# 11_-_CPU_-_JTAG_CONTROL.net
KiCad netlist of a schematic drawn in Altium Designer
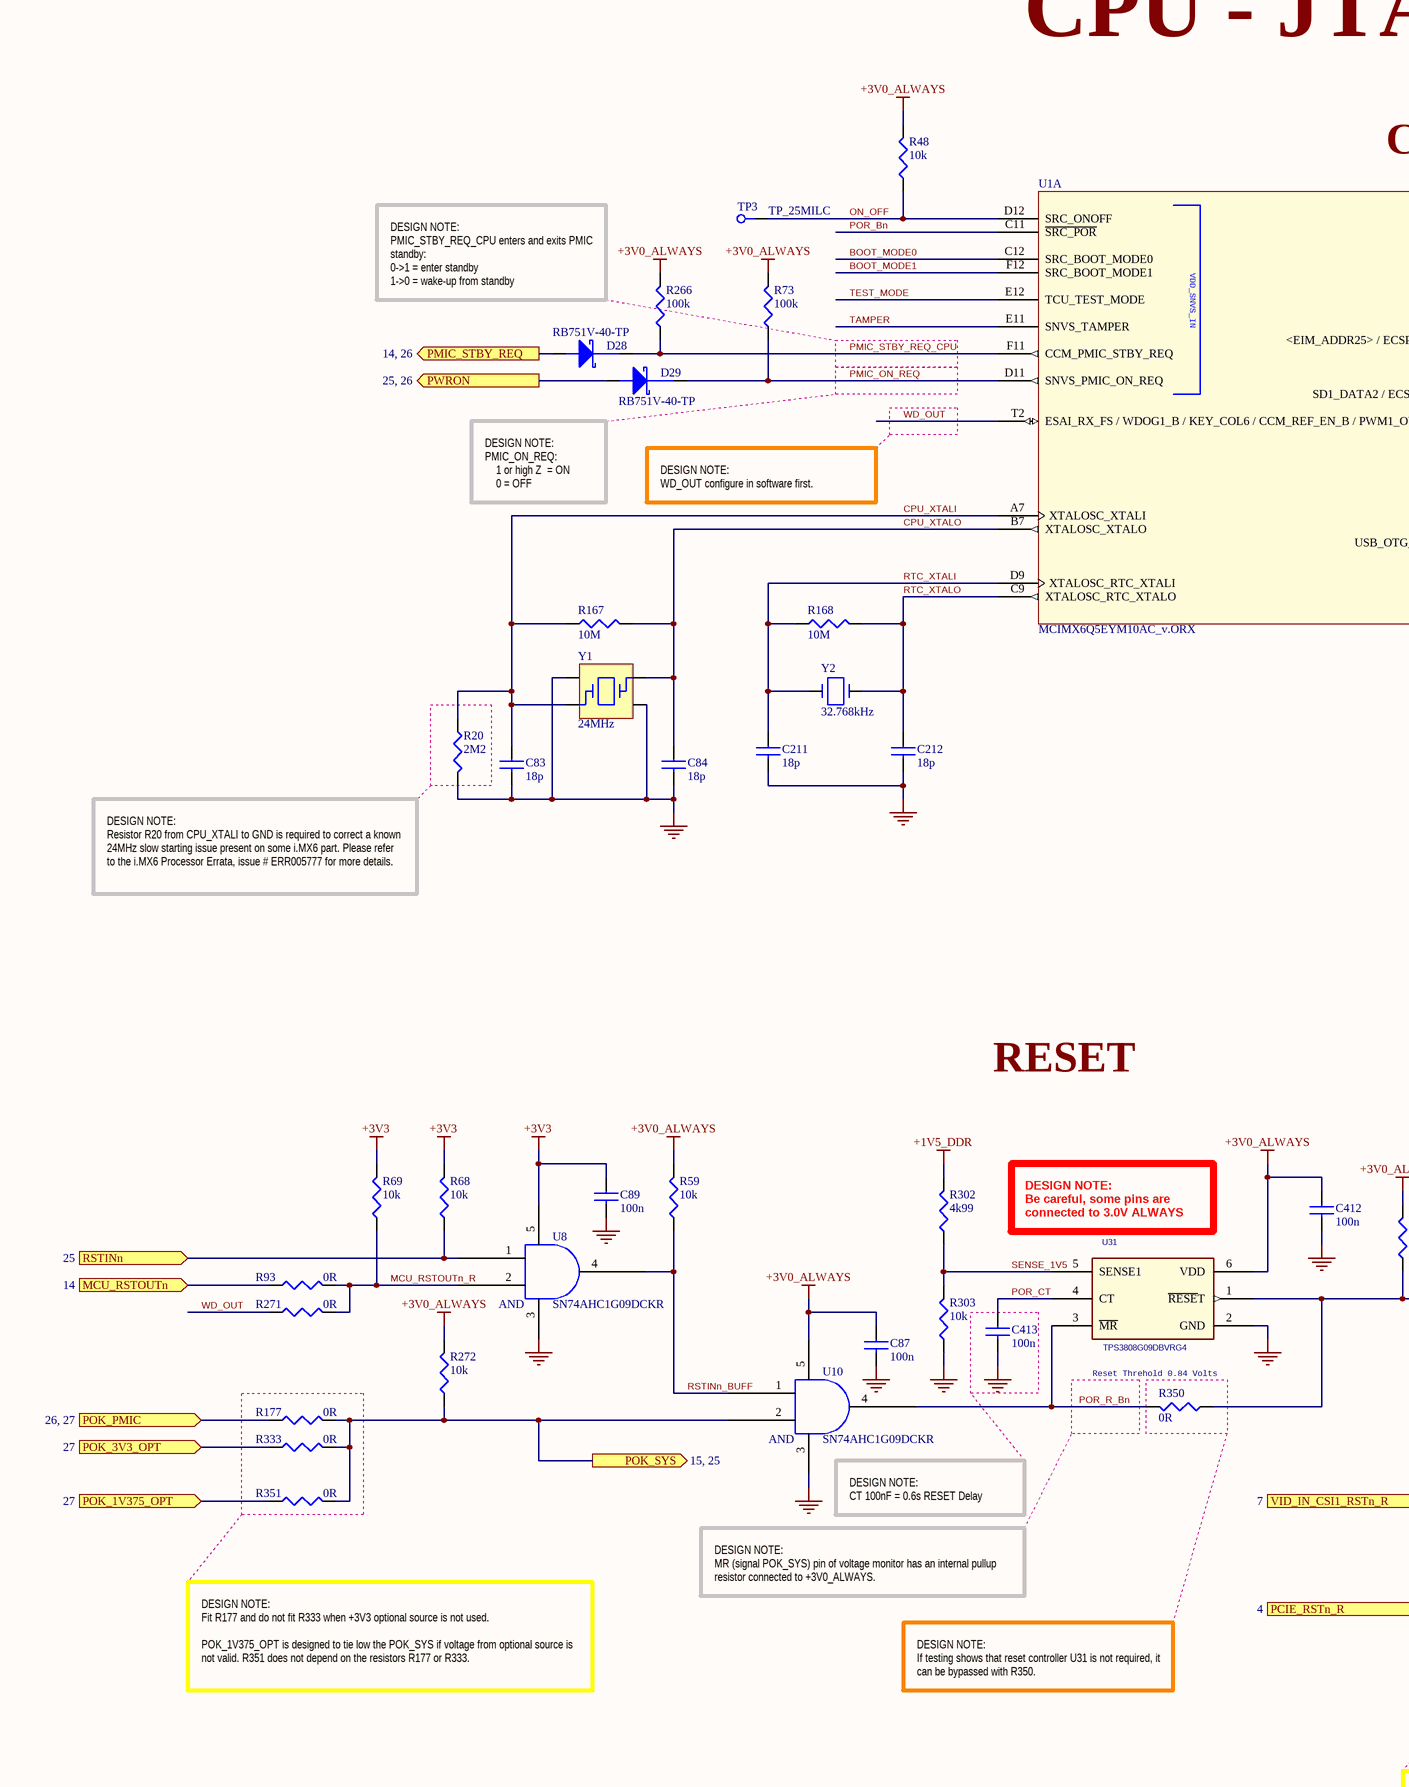
[diagram p0: [11] - CPU - JTAG, CONTROL.SchDoc, left]
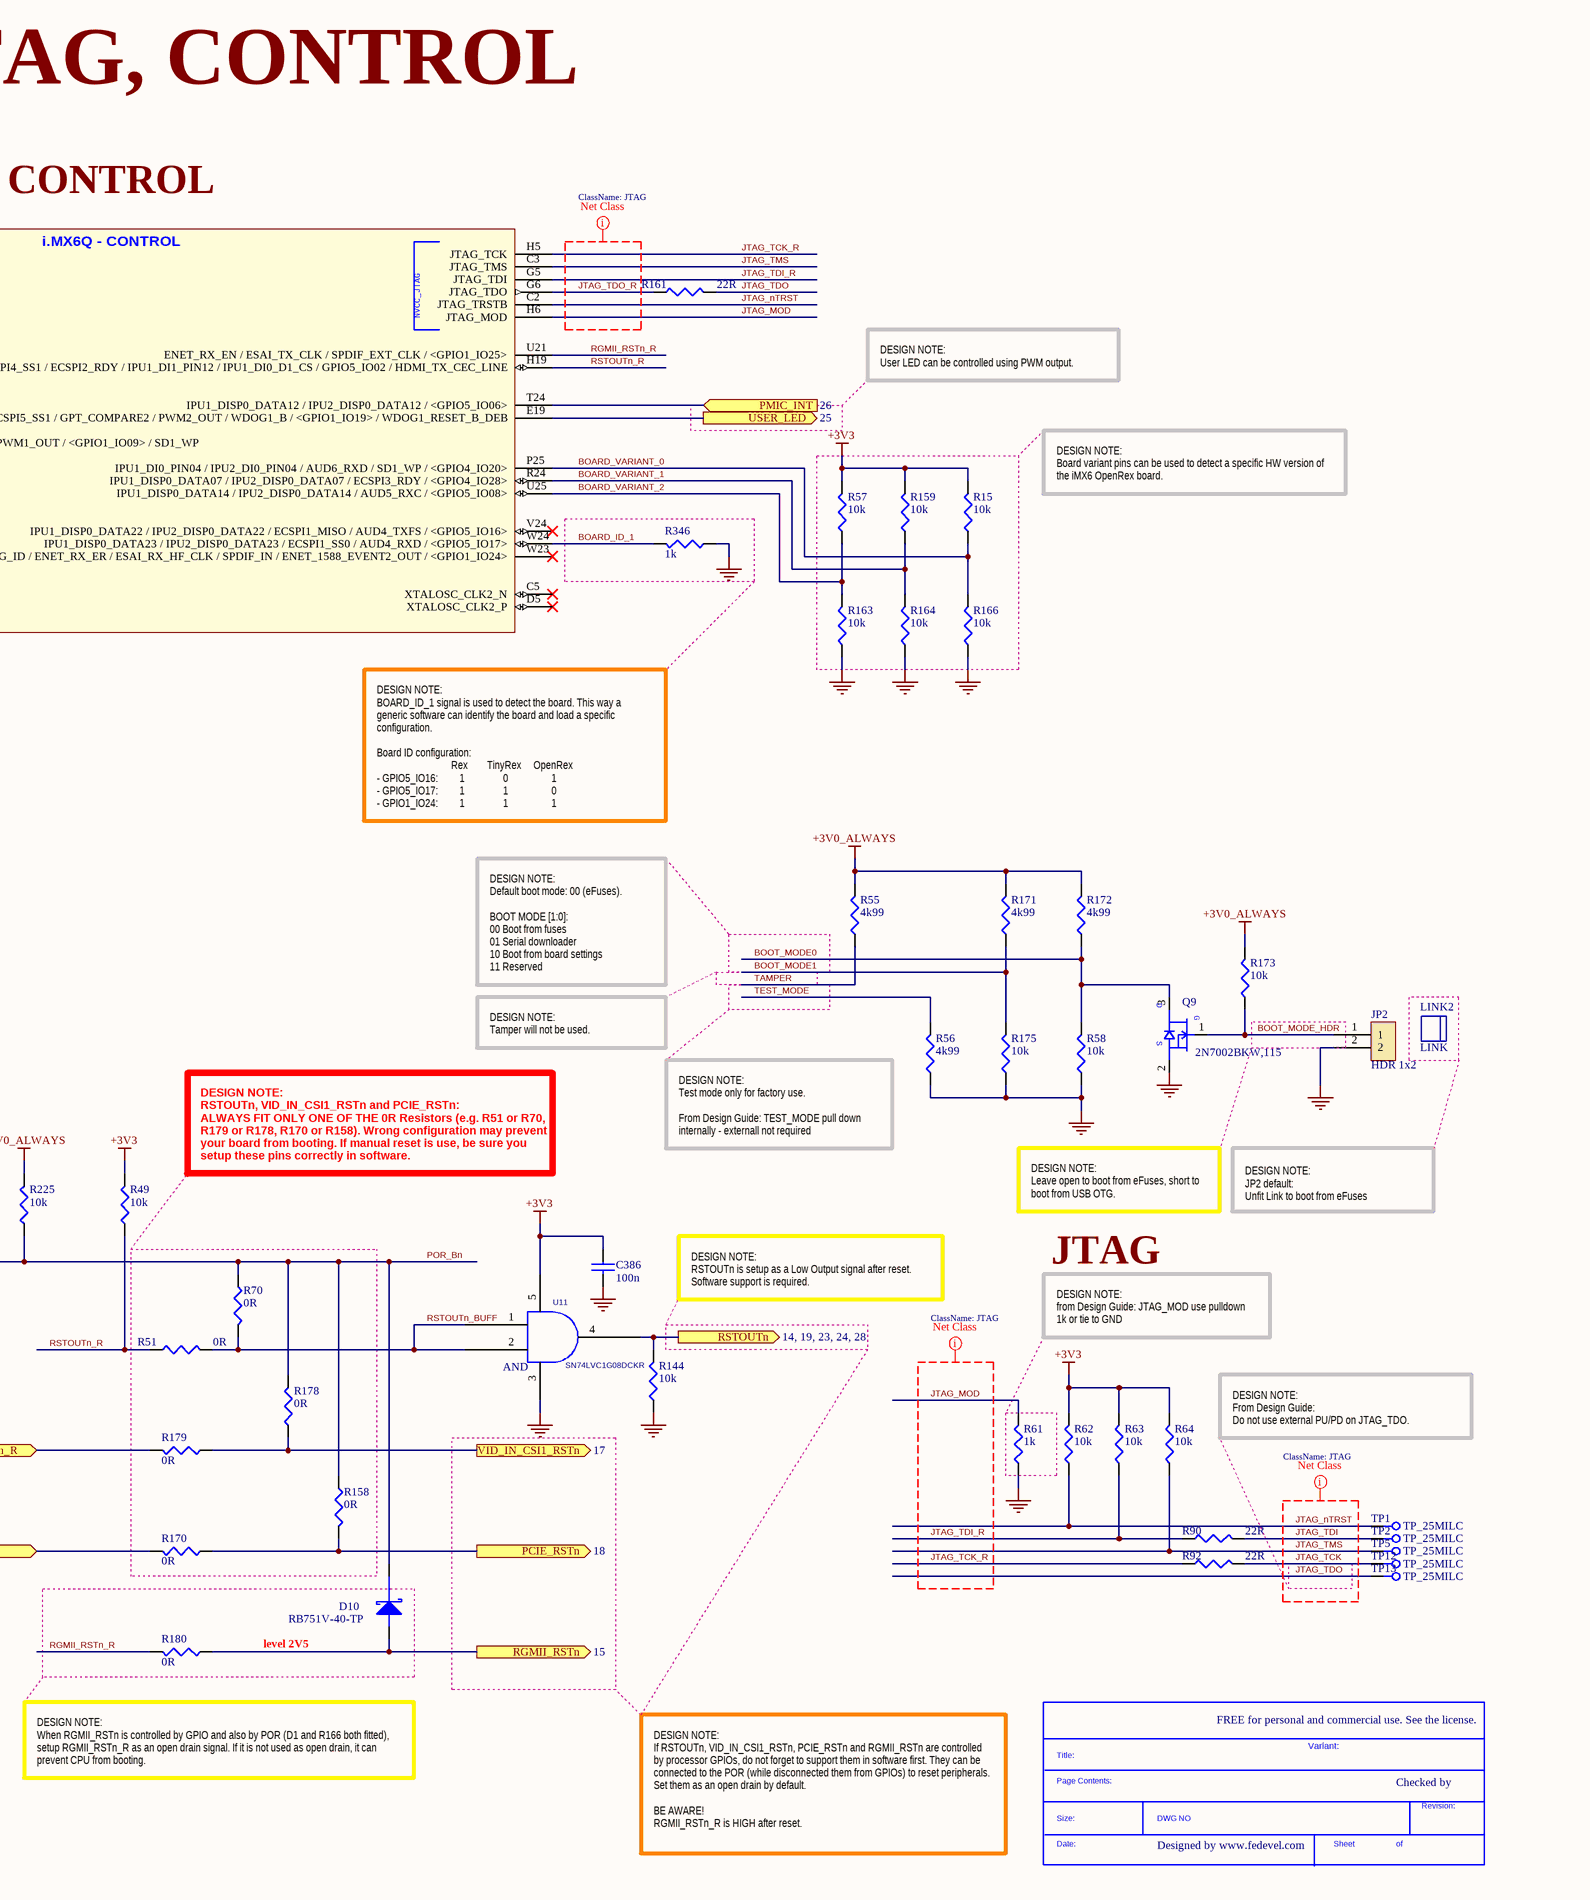
[diagram p1: [11] - CPU - JTAG, CONTROL.SchDoc, right]

(export (version "E")
  (design (tool "Eeschema 10.0.6"))
  (components
    (comp (ref "C83")
      (value "18p")
      (footprint "C0402")
      (description "CAP CER 18PF 50V C0G 5% 0402")
      (fields
        (field (name "MANUFACTURER") "TDK Corporation")
        (field (name "MANUFACTURER PART NUMBER") "C1005C0G1H180J")
      )
      (libsource (lib "Integrated_Library_FEDEVEL_APR_2015") (part "C1005C0G1H180J"))
    )
    (comp (ref "C84")
      (value "18p")
      (footprint "C0402")
      (description "CAP CER 18PF 50V C0G 5% 0402")
      (fields
        (field (name "MANUFACTURER") "TDK Corporation")
        (field (name "MANUFACTURER PART NUMBER") "C1005C0G1H180J")
      )
      (libsource (lib "Integrated_Library_FEDEVEL_APR_2015") (part "C1005C0G1H180J"))
    )
    (comp (ref "C87")
      (value "100n")
      (footprint "C0402")
      (description "CAP CER .10UF 50V X5R 10% 0402")
      (fields
        (field (name "MANUFACTURER") "TDK Corporation")
        (field (name "MANUFACTURER PART NUMBER") "C1005X5R1H104K")
      )
      (libsource (lib "Integrated_Library_FEDEVEL_APR_2015") (part "C1005X5R1H104K"))
    )
    (comp (ref "C89")
      (value "100n")
      (footprint "C0402")
      (description "CAP CER .10UF 50V X5R 10% 0402")
      (fields
        (field (name "MANUFACTURER") "TDK Corporation")
        (field (name "MANUFACTURER PART NUMBER") "C1005X5R1H104K")
      )
      (libsource (lib "Integrated_Library_FEDEVEL_APR_2015") (part "C1005X5R1H104K"))
    )
    (comp (ref "C211")
      (value "18p")
      (footprint "C0201")
      (description "CAP CER 18PF 50V 5% C0G 0201")
      (fields
        (field (name "MANUFACTURER") "TDK Corporation")
        (field (name "MANUFACTURER PART NUMBER") "C0603C0G1H180J030BA")
        (field (name ".CREATOR") "MM")
        (field (name ".CHECKED PCB") "MM")
        (field (name ".CHECKED SCH") "MM")
      )
      (libsource (lib "Integrated_Library_FEDEVEL_0201") (part "C0603C0G1H180J030BA"))
    )
    (comp (ref "C212")
      (value "18p")
      (footprint "C0201")
      (description "CAP CER 18PF 50V 5% C0G 0201")
      (fields
        (field (name "MANUFACTURER") "TDK Corporation")
        (field (name "MANUFACTURER PART NUMBER") "C0603C0G1H180J030BA")
        (field (name ".CREATOR") "MM")
        (field (name ".CHECKED PCB") "MM")
        (field (name ".CHECKED SCH") "MM")
      )
      (libsource (lib "Integrated_Library_FEDEVEL_0201") (part "C0603C0G1H180J030BA"))
    )
    (comp (ref "C386")
      (value "100n")
      (footprint "C0402")
      (description "CAP CER .10UF 50V X5R 10% 0402")
      (fields
        (field (name "MANUFACTURER") "TDK Corporation")
        (field (name "MANUFACTURER PART NUMBER") "C1005X5R1H104K")
      )
      (libsource (lib "Integrated_Library_FEDEVEL_APR_2015") (part "C1005X5R1H104K"))
    )
    (comp (ref "C412")
      (value "100n")
      (footprint "C0402")
      (description "CAP CER .10UF 50V X5R 10% 0402")
      (fields
        (field (name "MANUFACTURER") "TDK Corporation")
        (field (name "MANUFACTURER PART NUMBER") "C1005X5R1H104K")
      )
      (libsource (lib "Integrated_Library_FEDEVEL_APR_2015") (part "C1005X5R1H104K"))
    )
    (comp (ref "C413")
      (value "100n")
      (footprint "C0402")
      (description "CAP CER .10UF 50V X5R 10% 0402")
      (fields
        (field (name "MANUFACTURER") "TDK Corporation")
        (field (name "MANUFACTURER PART NUMBER") "C1005X5R1H104K")
      )
      (libsource (lib "Integrated_Library_FEDEVEL_APR_2015") (part "C1005X5R1H104K"))
    )
    (comp (ref "D10")
      (value "RB751V-40-TP")
      (footprint "SOD323")
      (description "DIODE SCHTKY 30MA 30V SOD-323")
      (fields (field (name "MANUFACTURER") "Micro Commercial Co"))
      (libsource (lib "Integrated_Library_FEDEVEL_APR_2015") (part "RB751V-40-TP"))
    )
    (comp (ref "D28")
      (value "RB751V-40-TP")
      (footprint "SOD323")
      (description "DIODE SCHTKY 30MA 30V SOD-323")
      (fields (field (name "MANUFACTURER") "Micro Commercial Co"))
      (libsource (lib "Integrated_Library_FEDEVEL_APR_2015") (part "RB751V-40-TP"))
    )
    (comp (ref "D29")
      (value "RB751V-40-TP")
      (footprint "SOD323")
      (description "DIODE SCHTKY 30MA 30V SOD-323")
      (fields (field (name "MANUFACTURER") "Micro Commercial Co"))
      (libsource (lib "Integrated_Library_FEDEVEL_APR_2015") (part "RB751V-40-TP"))
    )
    (comp (ref "JP2")
      (value "HDR 1x2")
      (footprint "HDR_1x2_2.54MM")
      (description "BERGSTIK II .100\" SR STRAIGHT")
      (fields (field (name "MANUFACTURER") "FCI") (field (name "MANUFACTURER PART NUMBER") "68001-202HLF"))
      (libsource (lib "Integrated_Library_FEDEVEL_APR_2015") (part "68001-202HLF"))
    )
    (comp (ref "LINK2")
      (value "LINK")
      (description "CONN JUMPER SHORTING .100\" GOLD")
      (fields
        (field (name "MANUFACTURER") "Sullins Connector Solutions")
        (field (name "MANUFACTURER PART NUMBER") "QPC02SXGN-RC")
      )
      (libsource (lib "Integrated_Library_FEDEVEL_APR_2015") (part "QPC02SXGN-RC"))
    )
    (comp (ref "Q9")
      (value "2N7002BKW,115")
      (footprint "SC70_SOT323")
      (description "MOSFET N-CH 60V 310MA SOT323")
      (fields (field (name "MANUFACTURER") "NXP Semiconductors"))
      (libsource (lib "Integrated_Library_FEDEVEL_APR_2015") (part "2N7002BKW,115"))
    )
    (comp (ref "R15")
      (value "10k")
      (footprint "R0402")
      (description "RES 10.0K OHM 1/16W 1% 0402 SMD")
      (fields
        (field (name "MANUFACTURER") "Yageo")
        (field (name "MANUFACTURER PART NUMBER") "RC0402FR-0710KL")
      )
      (libsource (lib "Integrated_Library_FEDEVEL_APR_2015") (part "RC0402FR-0710KL"))
    )
    (comp (ref "R20")
      (value "2M2")
      (footprint "R0402")
      (description "RES 2.20M OHM 1/16W 1% 0402 SMD")
      (fields
        (field (name "MANUFACTURER") "Vishay Dale")
        (field (name "MANUFACTURER PART NUMBER") "CRCW04022M20FKED")
        (field (name ".CREATOR") "MM")
      )
      (libsource (lib "Integrated_Library_FEDEVEL_APR_2015") (part "CRCW04022M20FKED"))
    )
    (comp (ref "R48")
      (value "10k")
      (footprint "R0402")
      (description "RES 10.0K OHM 1/16W 1% 0402 SMD")
      (fields
        (field (name "MANUFACTURER") "Yageo")
        (field (name "MANUFACTURER PART NUMBER") "RC0402FR-0710KL")
      )
      (libsource (lib "Integrated_Library_FEDEVEL_APR_2015") (part "RC0402FR-0710KL"))
    )
    (comp (ref "R49")
      (value "10k")
      (footprint "R0402")
      (description "RES 10.0K OHM 1/16W 1% 0402 SMD")
      (fields
        (field (name "MANUFACTURER") "Yageo")
        (field (name "MANUFACTURER PART NUMBER") "RC0402FR-0710KL")
      )
      (libsource (lib "Integrated_Library_FEDEVEL_APR_2015") (part "RC0402FR-0710KL"))
    )
    (comp (ref "R51")
      (value "0R")
      (footprint "R0402")
      (description "RES 0.0 OHM 1/16W 0402 SMD")
      (fields
        (field (name "MANUFACTURER") "Yageo")
        (field (name "MANUFACTURER PART NUMBER") "RC0402JR-070RL")
      )
      (libsource (lib "Integrated_Library_FEDEVEL_APR_2015") (part "RC0402JR-070RL"))
    )
    (comp (ref "R55")
      (value "4k99")
      (footprint "R0201")
      (description "RES 4.99K OHM 1/20W 1% 0201")
      (fields
        (field (name "MANUFACTURER") "Stackpole Electronics Inc")
        (field (name "MANUFACTURER PART NUMBER") "RMCF0201FT4K99")
        (field (name ".CREATOR") "MM")
        (field (name ".CHECKED PCB") "MM")
        (field (name ".CHECKED SCH") "MM")
      )
      (libsource (lib "Integrated_Library_FEDEVEL_0201") (part "RMCF0201FT4K99"))
    )
    (comp (ref "R56")
      (value "4k99")
      (footprint "R0201")
      (description "RES 4.99K OHM 1/20W 1% 0201")
      (fields
        (field (name "MANUFACTURER") "Stackpole Electronics Inc")
        (field (name "MANUFACTURER PART NUMBER") "RMCF0201FT4K99")
        (field (name ".CREATOR") "MM")
        (field (name ".CHECKED PCB") "MM")
        (field (name ".CHECKED SCH") "MM")
      )
      (libsource (lib "Integrated_Library_FEDEVEL_0201") (part "RMCF0201FT4K99"))
    )
    (comp (ref "R57")
      (value "10k")
      (footprint "R0402")
      (description "RES 10.0K OHM 1/16W 1% 0402 SMD")
      (fields
        (field (name "MANUFACTURER") "Yageo")
        (field (name "MANUFACTURER PART NUMBER") "RC0402FR-0710KL")
      )
      (libsource (lib "Integrated_Library_FEDEVEL_APR_2015") (part "RC0402FR-0710KL"))
    )
    (comp (ref "R58")
      (value "10k")
      (footprint "R0402")
      (description "RES 10.0K OHM 1/16W 1% 0402 SMD")
      (fields
        (field (name "MANUFACTURER") "Yageo")
        (field (name "MANUFACTURER PART NUMBER") "RC0402FR-0710KL")
      )
      (libsource (lib "Integrated_Library_FEDEVEL_APR_2015") (part "RC0402FR-0710KL"))
    )
    (comp (ref "R59")
      (value "10k")
      (footprint "R0402")
      (description "RES 10.0K OHM 1/16W 1% 0402 SMD")
      (fields
        (field (name "MANUFACTURER") "Yageo")
        (field (name "MANUFACTURER PART NUMBER") "RC0402FR-0710KL")
      )
      (libsource (lib "Integrated_Library_FEDEVEL_APR_2015") (part "RC0402FR-0710KL"))
    )
    (comp (ref "R61")
      (value "1k")
      (footprint "R0201")
      (description "RES 1K OHM 1/20W 1% 0201 SMD")
      (fields
        (field (name "MANUFACTURER") "Yageo")
        (field (name "MANUFACTURER PART NUMBER") "RC0201FR-071KL")
        (field (name ".CREATOR") "MM")
        (field (name ".CHECKED PCB") "MM")
        (field (name ".CHECKED SCH") "MM")
      )
      (libsource (lib "Integrated_Library_FEDEVEL_0201") (part "RC0201FR-071KL"))
    )
    (comp (ref "R62")
      (value "10k")
      (footprint "R0402")
      (description "RES 10.0K OHM 1/16W 1% 0402 SMD")
      (fields
        (field (name "MANUFACTURER") "Yageo")
        (field (name "MANUFACTURER PART NUMBER") "RC0402FR-0710KL")
      )
      (libsource (lib "Integrated_Library_FEDEVEL_APR_2015") (part "RC0402FR-0710KL"))
    )
    (comp (ref "R63")
      (value "10k")
      (footprint "R0402")
      (description "RES 10.0K OHM 1/16W 1% 0402 SMD")
      (fields
        (field (name "MANUFACTURER") "Yageo")
        (field (name "MANUFACTURER PART NUMBER") "RC0402FR-0710KL")
      )
      (libsource (lib "Integrated_Library_FEDEVEL_APR_2015") (part "RC0402FR-0710KL"))
    )
    (comp (ref "R64")
      (value "10k")
      (footprint "R0402")
      (description "RES 10.0K OHM 1/16W 1% 0402 SMD")
      (fields
        (field (name "MANUFACTURER") "Yageo")
        (field (name "MANUFACTURER PART NUMBER") "RC0402FR-0710KL")
      )
      (libsource (lib "Integrated_Library_FEDEVEL_APR_2015") (part "RC0402FR-0710KL"))
    )
    (comp (ref "R68")
      (value "10k")
      (footprint "R0402")
      (description "RES 10.0K OHM 1/16W 1% 0402 SMD")
      (fields
        (field (name "MANUFACTURER") "Yageo")
        (field (name "MANUFACTURER PART NUMBER") "RC0402FR-0710KL")
      )
      (libsource (lib "Integrated_Library_FEDEVEL_APR_2015") (part "RC0402FR-0710KL"))
    )
    (comp (ref "R69")
      (value "10k")
      (footprint "R0402")
      (description "RES 10.0K OHM 1/16W 1% 0402 SMD")
      (fields
        (field (name "MANUFACTURER") "Yageo")
        (field (name "MANUFACTURER PART NUMBER") "RC0402FR-0710KL")
      )
      (libsource (lib "Integrated_Library_FEDEVEL_APR_2015") (part "RC0402FR-0710KL"))
    )
    (comp (ref "R70")
      (value "0R")
      (footprint "R0402")
      (description "RES 0.0 OHM 1/16W 0402 SMD")
      (fields
        (field (name "MANUFACTURER") "Yageo")
        (field (name "MANUFACTURER PART NUMBER") "RC0402JR-070RL")
      )
      (libsource (lib "Integrated_Library_FEDEVEL_APR_2015") (part "RC0402JR-070RL"))
    )
    (comp (ref "R73")
      (value "100k")
      (footprint "R0402")
      (description "RES 100K OHM 1/16W 1% 0402 SMD")
      (fields
        (field (name "MANUFACTURER") "Stackpole Electronics Inc")
        (field (name "MANUFACTURER PART NUMBER") "RMCF0402FT100K")
      )
      (libsource (lib "Integrated_Library_FEDEVEL_APR_2015") (part "RMCF0402FT100K"))
    )
    (comp (ref "R90")
      (value "22R")
      (footprint "R0402")
      (description "RES 22.0 OHM 1/16W 1% 0402 SMD")
      (fields
        (field (name "MANUFACTURER") "Yageo")
        (field (name "MANUFACTURER PART NUMBER") "RC0402FR-0722RL")
      )
      (libsource (lib "Integrated_Library_FEDEVEL_APR_2015") (part "RC0402FR-0722RL"))
    )
    (comp (ref "R92")
      (value "22R")
      (footprint "R0402")
      (description "RES 22.0 OHM 1/16W 1% 0402 SMD")
      (fields
        (field (name "MANUFACTURER") "Yageo")
        (field (name "MANUFACTURER PART NUMBER") "RC0402FR-0722RL")
      )
      (libsource (lib "Integrated_Library_FEDEVEL_APR_2015") (part "RC0402FR-0722RL"))
    )
    (comp (ref "R93")
      (value "0R")
      (footprint "R0402")
      (description "RES 0.0 OHM 1/16W 0402 SMD")
      (fields
        (field (name "MANUFACTURER") "Yageo")
        (field (name "MANUFACTURER PART NUMBER") "RC0402JR-070RL")
      )
      (libsource (lib "Integrated_Library_FEDEVEL_APR_2015") (part "RC0402JR-070RL"))
    )
    (comp (ref "R144")
      (value "10k")
      (footprint "R0402")
      (description "RES 10.0K OHM 1/16W 1% 0402 SMD")
      (fields
        (field (name "MANUFACTURER") "Yageo")
        (field (name "MANUFACTURER PART NUMBER") "RC0402FR-0710KL")
      )
      (libsource (lib "Integrated_Library_FEDEVEL_APR_2015") (part "RC0402FR-0710KL"))
    )
    (comp (ref "R158")
      (value "0R")
      (footprint "R0402")
      (description "RES 0.0 OHM 1/16W 0402 SMD")
      (fields
        (field (name "MANUFACTURER") "Yageo")
        (field (name "MANUFACTURER PART NUMBER") "RC0402JR-070RL")
      )
      (libsource (lib "Integrated_Library_FEDEVEL_APR_2015") (part "RC0402JR-070RL"))
    )
    (comp (ref "R159")
      (value "10k")
      (footprint "R0402")
      (description "RES 10.0K OHM 1/16W 1% 0402 SMD")
      (fields
        (field (name "MANUFACTURER") "Yageo")
        (field (name "MANUFACTURER PART NUMBER") "RC0402FR-0710KL")
      )
      (libsource (lib "Integrated_Library_FEDEVEL_APR_2015") (part "RC0402FR-0710KL"))
    )
    (comp (ref "R161")
      (value "22R")
      (footprint "R0402")
      (description "RES 22.0 OHM 1/16W 1% 0402 SMD")
      (fields
        (field (name "MANUFACTURER") "Yageo")
        (field (name "MANUFACTURER PART NUMBER") "RC0402FR-0722RL")
      )
      (libsource (lib "Integrated_Library_FEDEVEL_APR_2015") (part "RC0402FR-0722RL"))
    )
    (comp (ref "R163")
      (value "10k")
      (footprint "R0402")
      (description "RES 10.0K OHM 1/16W 1% 0402 SMD")
      (fields
        (field (name "MANUFACTURER") "Yageo")
        (field (name "MANUFACTURER PART NUMBER") "RC0402FR-0710KL")
      )
      (libsource (lib "Integrated_Library_FEDEVEL_APR_2015") (part "RC0402FR-0710KL"))
    )
    (comp (ref "R164")
      (value "10k")
      (footprint "R0402")
      (description "RES 10.0K OHM 1/16W 1% 0402 SMD")
      (fields
        (field (name "MANUFACTURER") "Yageo")
        (field (name "MANUFACTURER PART NUMBER") "RC0402FR-0710KL")
      )
      (libsource (lib "Integrated_Library_FEDEVEL_APR_2015") (part "RC0402FR-0710KL"))
    )
    (comp (ref "R166")
      (value "10k")
      (footprint "R0402")
      (description "RES 10.0K OHM 1/16W 1% 0402 SMD")
      (fields
        (field (name "MANUFACTURER") "Yageo")
        (field (name "MANUFACTURER PART NUMBER") "RC0402FR-0710KL")
      )
      (libsource (lib "Integrated_Library_FEDEVEL_APR_2015") (part "RC0402FR-0710KL"))
    )
    (comp (ref "R167")
      (value "10M")
      (footprint "R0402")
      (description "RES 10.0M OHM 1/16W 1% 0402 SMD")
      (fields
        (field (name "MANUFACTURER") "Vishay Dale")
        (field (name "MANUFACTURER PART NUMBER") "CRCW040210M0FKED")
        (field (name ".CHECKED PCB") "RF")
        (field (name ".CHECKED SCH") "RF")
      )
      (libsource (lib "Integrated_Library_FEDEVEL_APR_2015") (part "CRCW040210M0FKED"))
    )
    (comp (ref "R168")
      (value "10M")
      (footprint "R0201")
      (description "RES 10M OHM 1/20W 1% 0201 SMD")
      (fields
        (field (name "MANUFACTURER") "Rohm Semiconductor")
        (field (name "MANUFACTURER PART NUMBER") "MCR006YZPF1005")
        (field (name ".CREATOR") "MM")
        (field (name ".CHECKED PCB") "MM")
        (field (name ".CHECKED SCH") "MM")
      )
      (libsource (lib "Integrated_Library_FEDEVEL_0201") (part "MCR006YZPF1005"))
    )
    (comp (ref "R170")
      (value "0R")
      (footprint "R0402")
      (description "RES 0.0 OHM 1/16W 0402 SMD")
      (fields
        (field (name "MANUFACTURER") "Yageo")
        (field (name "MANUFACTURER PART NUMBER") "RC0402JR-070RL")
      )
      (libsource (lib "Integrated_Library_FEDEVEL_APR_2015") (part "RC0402JR-070RL"))
    )
    (comp (ref "R171")
      (value "4k99")
      (footprint "R0402")
      (description "RES TF 4.99K OHM 1% 1/16W 0402")
      (fields
        (field (name "MANUFACTURER") "Stackpole Electronics Inc")
        (field (name "MANUFACTURER PART NUMBER") "RMCF0402FT4K99")
      )
      (libsource (lib "Integrated_Library_FEDEVEL_APR_2015") (part "RMCF0402FT4K99"))
    )
    (comp (ref "R172")
      (value "4k99")
      (footprint "R0402")
      (description "RES TF 4.99K OHM 1% 1/16W 0402")
      (fields
        (field (name "MANUFACTURER") "Stackpole Electronics Inc")
        (field (name "MANUFACTURER PART NUMBER") "RMCF0402FT4K99")
      )
      (libsource (lib "Integrated_Library_FEDEVEL_APR_2015") (part "RMCF0402FT4K99"))
    )
    (comp (ref "R173")
      (value "10k")
      (footprint "R0402")
      (description "RES 10.0K OHM 1/16W 1% 0402 SMD")
      (fields
        (field (name "MANUFACTURER") "Yageo")
        (field (name "MANUFACTURER PART NUMBER") "RC0402FR-0710KL")
      )
      (libsource (lib "Integrated_Library_FEDEVEL_APR_2015") (part "RC0402FR-0710KL"))
    )
    (comp (ref "R175")
      (value "10k")
      (footprint "R0402")
      (description "RES 10.0K OHM 1/16W 1% 0402 SMD")
      (fields
        (field (name "MANUFACTURER") "Yageo")
        (field (name "MANUFACTURER PART NUMBER") "RC0402FR-0710KL")
      )
      (libsource (lib "Integrated_Library_FEDEVEL_APR_2015") (part "RC0402FR-0710KL"))
    )
    (comp (ref "R177")
      (value "0R")
      (footprint "R0402")
      (description "RES 0.0 OHM 1/16W 0402 SMD")
      (fields
        (field (name "MANUFACTURER") "Yageo")
        (field (name "MANUFACTURER PART NUMBER") "RC0402JR-070RL")
      )
      (libsource (lib "Integrated_Library_FEDEVEL_APR_2015") (part "RC0402JR-070RL"))
    )
    (comp (ref "R178")
      (value "0R")
      (footprint "R0402")
      (description "RES 0.0 OHM 1/16W 0402 SMD")
      (fields
        (field (name "MANUFACTURER") "Yageo")
        (field (name "MANUFACTURER PART NUMBER") "RC0402JR-070RL")
      )
      (libsource (lib "Integrated_Library_FEDEVEL_APR_2015") (part "RC0402JR-070RL"))
    )
    (comp (ref "R179")
      (value "0R")
      (footprint "R0402")
      (description "RES 0.0 OHM 1/16W 0402 SMD")
      (fields
        (field (name "MANUFACTURER") "Yageo")
        (field (name "MANUFACTURER PART NUMBER") "RC0402JR-070RL")
      )
      (libsource (lib "Integrated_Library_FEDEVEL_APR_2015") (part "RC0402JR-070RL"))
    )
    (comp (ref "R180")
      (value "0R")
      (footprint "R0402")
      (description "RES 0.0 OHM 1/16W 0402 SMD")
      (fields
        (field (name "MANUFACTURER") "Yageo")
        (field (name "MANUFACTURER PART NUMBER") "RC0402JR-070RL")
      )
      (libsource (lib "Integrated_Library_FEDEVEL_APR_2015") (part "RC0402JR-070RL"))
    )
    (comp (ref "R225")
      (value "10k")
      (footprint "R0402")
      (description "RES 10.0K OHM 1/16W 1% 0402 SMD")
      (fields
        (field (name "MANUFACTURER") "Yageo")
        (field (name "MANUFACTURER PART NUMBER") "RC0402FR-0710KL")
      )
      (libsource (lib "Integrated_Library_FEDEVEL_APR_2015") (part "RC0402FR-0710KL"))
    )
    (comp (ref "R266")
      (value "100k")
      (footprint "R0402")
      (description "RES 100K OHM 1/16W 1% 0402 SMD")
      (fields
        (field (name "MANUFACTURER") "Stackpole Electronics Inc")
        (field (name "MANUFACTURER PART NUMBER") "RMCF0402FT100K")
      )
      (libsource (lib "Integrated_Library_FEDEVEL_APR_2015") (part "RMCF0402FT100K"))
    )
    (comp (ref "R271")
      (value "0R")
      (footprint "R0402")
      (description "RES 0.0 OHM 1/16W 0402 SMD")
      (fields
        (field (name "MANUFACTURER") "Yageo")
        (field (name "MANUFACTURER PART NUMBER") "RC0402JR-070RL")
      )
      (libsource (lib "Integrated_Library_FEDEVEL_APR_2015") (part "RC0402JR-070RL"))
    )
    (comp (ref "R272")
      (value "10k")
      (footprint "R0402")
      (description "RES 10.0K OHM 1/16W 1% 0402 SMD")
      (fields
        (field (name "MANUFACTURER") "Yageo")
        (field (name "MANUFACTURER PART NUMBER") "RC0402FR-0710KL")
      )
      (libsource (lib "Integrated_Library_FEDEVEL_APR_2015") (part "RC0402FR-0710KL"))
    )
    (comp (ref "R302")
      (value "4k99")
      (footprint "R0402")
      (description "RES TF 4.99K OHM 1% 1/16W 0402")
      (fields
        (field (name "MANUFACTURER") "Stackpole Electronics Inc")
        (field (name "MANUFACTURER PART NUMBER") "RMCF0402FT4K99")
      )
      (libsource (lib "Integrated_Library_FEDEVEL_APR_2015") (part "RMCF0402FT4K99"))
    )
    (comp (ref "R303")
      (value "10k")
      (footprint "R0402")
      (description "RES 10.0K OHM 1/16W 1% 0402 SMD")
      (fields
        (field (name "MANUFACTURER") "Yageo")
        (field (name "MANUFACTURER PART NUMBER") "RC0402FR-0710KL")
      )
      (libsource (lib "Integrated_Library_FEDEVEL_APR_2015") (part "RC0402FR-0710KL"))
    )
    (comp (ref "R333")
      (value "0R")
      (footprint "R0402")
      (description "RES 0.0 OHM 1/16W 0402 SMD")
      (fields
        (field (name "MANUFACTURER") "Yageo")
        (field (name "MANUFACTURER PART NUMBER") "RC0402JR-070RL")
      )
      (libsource (lib "Integrated_Library_FEDEVEL_APR_2015") (part "RC0402JR-070RL"))
    )
    (comp (ref "R346")
      (value "1k")
      (footprint "R0402")
      (description "RES 1.00K OHM 1/16W 1% 0402 SMD")
      (fields
        (field (name "MANUFACTURER") "Yageo")
        (field (name "MANUFACTURER PART NUMBER") "RC0402FR-071KL")
      )
      (libsource (lib "Integrated_Library_FEDEVEL_APR_2015") (part "RC0402FR-071KL"))
    )
    (comp (ref "R350")
      (value "0R")
      (footprint "R0402")
      (description "RES 0.0 OHM 1/16W 0402 SMD")
      (fields
        (field (name "MANUFACTURER") "Yageo")
        (field (name "MANUFACTURER PART NUMBER") "RC0402JR-070RL")
      )
      (libsource (lib "Integrated_Library_FEDEVEL_APR_2015") (part "RC0402JR-070RL"))
    )
    (comp (ref "R351")
      (value "0R")
      (footprint "R0402")
      (description "RES 0.0 OHM 1/16W 0402 SMD")
      (fields
        (field (name "MANUFACTURER") "Yageo")
        (field (name "MANUFACTURER PART NUMBER") "RC0402JR-070RL")
      )
      (libsource (lib "Integrated_Library_FEDEVEL_APR_2015") (part "RC0402JR-070RL"))
    )
    (comp (ref "TP1")
      (value "TP_25MILC")
      (footprint "TP_25C")
      (description "Test Point 25mil")
      (libsource (lib "Integrated_Library_FEDEVEL_APR_2015") (part "TP_25MILC"))
    )
    (comp (ref "TP2")
      (value "TP_25MILC")
      (footprint "TP_25C")
      (description "Test Point 25mil")
      (libsource (lib "Integrated_Library_FEDEVEL_APR_2015") (part "TP_25MILC"))
    )
    (comp (ref "TP3")
      (value "TP_25MILC")
      (footprint "TP_25C")
      (description "Test Point 25mil")
      (libsource (lib "Integrated_Library_FEDEVEL_APR_2015") (part "TP_25MILC"))
    )
    (comp (ref "TP5")
      (value "TP_25MILC")
      (footprint "TP_25C")
      (description "Test Point 25mil")
      (libsource (lib "Integrated_Library_FEDEVEL_APR_2015") (part "TP_25MILC"))
    )
    (comp (ref "TP12")
      (value "TP_25MILC")
      (footprint "TP_25C")
      (description "Test Point 25mil")
      (libsource (lib "Integrated_Library_FEDEVEL_APR_2015") (part "TP_25MILC"))
    )
    (comp (ref "TP13")
      (value "TP_25MILC")
      (footprint "TP_25C")
      (description "Test Point 25mil")
      (libsource (lib "Integrated_Library_FEDEVEL_APR_2015") (part "TP_25MILC"))
    )
    (comp (ref "U1")
      (value "MCIMX6Q5EYM10AC_v.ORX")
      (footprint "PBGA624")
      (description "IC MCU 32BIT ARM QUAD 624FCBGA")
      (fields
        (field (name "MANUFACTURER") "Freescale Semiconductor")
        (field (name "MANUFACTURER PART NUMBER") "MCIMX6Q5EYM10AC")
        (field (name ".CREATOR") "MM")
        (field (name ".CHECKED PCB") "MM, checked by RF")
      )
      (libsource (lib "Integrated_Library_FEDEVEL_APR_2015") (part "MCIMX6Q5EYM10AC_v.ORX"))
    )
    (comp (ref "U8")
      (value "SN74AHC1G09DCKR")
      (footprint "SC70_5")
      (description "IC GATE AND 1CH 2-INP SC-70-5")
      (fields
        (field (name "MANUFACTURER") "Texas Instruments")
        (field (name ".CREATOR") "MM")
        (field (name ".CHECKED SCH") "MM")
        (field (name ".CHECKED PCB") "RF, used by MM")
      )
      (libsource (lib "Integrated_Library_FEDEVEL_APR_2015") (part "SN74AHC1G09DCKR"))
    )
    (comp (ref "U10")
      (value "SN74AHC1G09DCKR")
      (footprint "SC70_5")
      (description "IC GATE AND 1CH 2-INP SC-70-5")
      (fields
        (field (name "MANUFACTURER") "Texas Instruments")
        (field (name ".CREATOR") "MM")
        (field (name ".CHECKED SCH") "MM")
        (field (name ".CHECKED PCB") "RF, used by MM")
      )
      (libsource (lib "Integrated_Library_FEDEVEL_APR_2015") (part "SN74AHC1G09DCKR"))
    )
    (comp (ref "U11")
      (value "SN74LVC1G08DCKR")
      (footprint "SC70_5")
      (description "SINGLE POSITIVE AND GATE SC-70")
      (fields (field (name "MANUFACTURER") "Texas Instruments"))
      (libsource (lib "Integrated_Library_FEDEVEL_APR_2015") (part "SN74LVC1G08DCKR"))
    )
    (comp (ref "U31")
      (value "TPS3808G09DBVRG4")
      (footprint "DBV_SOT_23_6")
      (description "IC VOLT SUPERVISOR 0.9V SOT23-6")
      (fields (field (name "PART #") "102020-0009R") (field (name "MANUFACTURER") "Texas Instruments"))
      (libsource (lib "Integrated_Library_FEDEVEL_APR_2015") (part "TPS3808G09DBVR"))
    )
    (comp (ref "Y1")
      (value "24MHz")
      (footprint "ABM8")
      (description "CRYSTAL 24MHZ 18PF SMD")
      (fields
        (field (name "MANUFACTURER") "Abracon Corporation")
        (field (name "MANUFACTURER PART NUMBER") "ABM8-24.000MHZ-R60-D-1-W-T")
        (field (name ".CREATOR") "MM")
        (field (name ".CHECKED PCB") "MM")
        (field (name ".CHECKED SCH") "MM")
      )
      (libsource (lib "Integrated_Library_FEDEVEL_APR_2015") (part "ABM8-24.000MHZ-R60-D-1-W-T"))
    )
    (comp (ref "Y2")
      (value "32.768kHz")
      (footprint "ABS06")
      (description "CRYSTAL 32.768 KHZ 9.0 PF SMD")
      (fields
        (field (name "MANUFACTURER") "Abracon Corporation")
        (field (name "MANUFACTURER PART NUMBER") "ABS06-32.768KHZ-9-1-T")
      )
      (libsource (lib "Integrated_Library_FEDEVEL_APR_2015") (part "ABS06-32.768KHZ-9-1-T"))
    )
  )
  (nets
    (net (code "1") (name "+1V5_DDR") (class "Default")
      (node (ref "R302") (pin "2") (pinfunction "2_2") (pintype "passive"))
    )
    (net (code "2") (name "+3V0_ALWAYS") (class "Default")
      (node (ref "C412") (pin "1") (pinfunction "1_1") (pintype "passive"))
      (node (ref "C87") (pin "1") (pinfunction "1_1") (pintype "passive"))
      (node (ref "R171") (pin "2") (pinfunction "2_2") (pintype "passive"))
      (node (ref "R172") (pin "2") (pinfunction "2_2") (pintype "passive"))
      (node (ref "R173") (pin "2") (pinfunction "2_2") (pintype "passive"))
      (node (ref "R225") (pin "2") (pinfunction "2_2") (pintype "passive"))
      (node (ref "R266") (pin "2") (pinfunction "2_2") (pintype "passive"))
      (node (ref "R272") (pin "2") (pinfunction "2_2") (pintype "passive"))
      (node (ref "R48") (pin "2") (pinfunction "2_2") (pintype "passive"))
      (node (ref "R55") (pin "2") (pinfunction "2_2") (pintype "passive"))
      (node (ref "R59") (pin "2") (pinfunction "2_2") (pintype "passive"))
      (node (ref "R73") (pin "2") (pinfunction "2_2") (pintype "passive"))
      (node (ref "U10") (pin "5") (pinfunction "VCC_5") (pintype "power_in"))
      (node (ref "U31") (pin "6") (pinfunction "VDD_6") (pintype "passive"))
    )
    (net (code "3") (name "+3V3") (class "Default")
      (node (ref "C386") (pin "1") (pinfunction "1_1") (pintype "passive"))
      (node (ref "C89") (pin "1") (pinfunction "1_1") (pintype "passive"))
      (node (ref "R15") (pin "2") (pinfunction "2_2") (pintype "passive"))
      (node (ref "R159") (pin "2") (pinfunction "2_2") (pintype "passive"))
      (node (ref "R49") (pin "2") (pinfunction "2_2") (pintype "passive"))
      (node (ref "R57") (pin "2") (pinfunction "2_2") (pintype "passive"))
      (node (ref "R62") (pin "2") (pinfunction "2_2") (pintype "passive"))
      (node (ref "R63") (pin "2") (pinfunction "2_2") (pintype "passive"))
      (node (ref "R64") (pin "2") (pinfunction "2_2") (pintype "passive"))
      (node (ref "R68") (pin "2") (pinfunction "2_2") (pintype "passive"))
      (node (ref "R69") (pin "2") (pinfunction "2_2") (pintype "passive"))
      (node (ref "U11") (pin "5") (pinfunction "VCC_5") (pintype "power_in"))
      (node (ref "U8") (pin "5") (pinfunction "VCC_5") (pintype "power_in"))
    )
    (net (code "4") (name "/BOARD_ID_1") (class "Default")
      (node (ref "R346") (pin "2") (pinfunction "2_2") (pintype "passive"))
      (node (ref "U1") (pin "W24") (pinfunction "IPU1_DISP0_DATA23_/_IPU2_DISP0_DATA23_/_ECSPI1_SS0_/_AUD4_RXD_/_<GPIO5_IO17>_W24") (pintype "bidirectional"))
    )
    (net (code "5") (name "/BOARD_VARIANT_0") (class "Default")
      (node (ref "R15") (pin "1") (pinfunction "1_1") (pintype "passive"))
      (node (ref "R166") (pin "2") (pinfunction "2_2") (pintype "passive"))
      (node (ref "U1") (pin "P25") (pinfunction "IPU1_DI0_PIN04_/_IPU2_DI0_PIN04_/_AUD6_RXD_/_SD1_WP_/_<GPIO4_IO20>_P25") (pintype "passive"))
    )
    (net (code "6") (name "/BOARD_VARIANT_1") (class "Default")
      (node (ref "R159") (pin "1") (pinfunction "1_1") (pintype "passive"))
      (node (ref "R164") (pin "2") (pinfunction "2_2") (pintype "passive"))
      (node (ref "U1") (pin "R24") (pinfunction "IPU1_DISP0_DATA07_/_IPU2_DISP0_DATA07_/_ECSPI3_RDY_/_<GPIO4_IO28>_R24") (pintype "bidirectional"))
    )
    (net (code "7") (name "/BOARD_VARIANT_2") (class "Default")
      (node (ref "R163") (pin "2") (pinfunction "2_2") (pintype "passive"))
      (node (ref "R57") (pin "1") (pinfunction "1_1") (pintype "passive"))
      (node (ref "U1") (pin "U25") (pinfunction "IPU1_DISP0_DATA14_/_IPU2_DISP0_DATA14_/_AUD5_RXC_/_<GPIO5_IO08>_U25") (pintype "bidirectional"))
    )
    (net (code "8") (name "/BOOT_MODE0") (class "Default")
      (node (ref "Q9") (pin "3") (pinfunction "DRAIN_3") (pintype "passive"))
      (node (ref "R172") (pin "1") (pinfunction "1_1") (pintype "passive"))
      (node (ref "R58") (pin "2") (pinfunction "2_2") (pintype "passive"))
      (node (ref "U1") (pin "C12") (pinfunction "SRC_BOOT_MODE0_C12") (pintype "passive"))
    )
    (net (code "9") (name "/BOOT_MODE1") (class "Default")
      (node (ref "R171") (pin "1") (pinfunction "1_1") (pintype "passive"))
      (node (ref "R175") (pin "2") (pinfunction "2_2") (pintype "passive"))
      (node (ref "U1") (pin "F12") (pinfunction "SRC_BOOT_MODE1_F12") (pintype "passive"))
    )
    (net (code "10") (name "/BOOT_MODE_HDR") (class "Default")
      (node (ref "JP2") (pin "1") (pinfunction "1_1") (pintype "passive"))
      (node (ref "Q9") (pin "1") (pinfunction "GATE_1") (pintype "passive"))
      (node (ref "R173") (pin "1") (pinfunction "1_1") (pintype "passive"))
    )
    (net (code "11") (name "/CPU_XTALI") (class "Default")
      (node (ref "C83") (pin "1") (pinfunction "1_1") (pintype "passive"))
      (node (ref "R167") (pin "1") (pinfunction "1_1") (pintype "passive"))
      (node (ref "R20") (pin "1") (pinfunction "1_1") (pintype "passive"))
      (node (ref "U1") (pin "A7") (pinfunction "XTALOSC_XTALI_A7") (pintype "passive"))
      (node (ref "Y1") (pin "3") (pinfunction "3_3") (pintype "passive"))
    )
    (net (code "12") (name "/CPU_XTALO") (class "Default")
      (node (ref "C84") (pin "1") (pinfunction "1_1") (pintype "passive"))
      (node (ref "R167") (pin "2") (pinfunction "2_2") (pintype "passive"))
      (node (ref "U1") (pin "B7") (pinfunction "XTALOSC_XTALO_B7") (pintype "output"))
      (node (ref "Y1") (pin "1") (pinfunction "1_1") (pintype "passive"))
    )
    (net (code "13") (name "/JTAG_MOD") (class "Default")
      (node (ref "R61") (pin "2") (pinfunction "2_2") (pintype "passive"))
      (node (ref "U1") (pin "H6") (pinfunction "JTAG_MOD_H6") (pintype "passive"))
    )
    (net (code "14") (name "/JTAG_TCK") (class "Default")
      (node (ref "R92") (pin "2") (pinfunction "2_2") (pintype "passive"))
      (node (ref "TP12") (pin "1") (pinfunction "1_1") (pintype "passive"))
    )
    (net (code "15") (name "/JTAG_TCK_R") (class "Default")
      (node (ref "R92") (pin "1") (pinfunction "1_1") (pintype "passive"))
      (node (ref "U1") (pin "H5") (pinfunction "JTAG_TCK_H5") (pintype "passive"))
    )
    (net (code "16") (name "/JTAG_TDI") (class "Default")
      (node (ref "R90") (pin "2") (pinfunction "2_2") (pintype "passive"))
      (node (ref "TP2") (pin "1") (pinfunction "1_1") (pintype "passive"))
    )
    (net (code "17") (name "/JTAG_TDI_R") (class "Default")
      (node (ref "R63") (pin "1") (pinfunction "1_1") (pintype "passive"))
      (node (ref "R90") (pin "1") (pinfunction "1_1") (pintype "passive"))
      (node (ref "U1") (pin "G5") (pinfunction "JTAG_TDI_G5") (pintype "passive"))
    )
    (net (code "18") (name "/JTAG_TDO") (class "Default")
      (node (ref "R161") (pin "2") (pinfunction "2_2") (pintype "passive"))
      (node (ref "TP13") (pin "1") (pinfunction "1_1") (pintype "passive"))
    )
    (net (code "19") (name "/JTAG_TDO_R") (class "Default")
      (node (ref "R161") (pin "1") (pinfunction "1_1") (pintype "passive"))
      (node (ref "U1") (pin "G6") (pinfunction "JTAG_TDO_G6") (pintype "output"))
    )
    (net (code "20") (name "/JTAG_TMS") (class "Default")
      (node (ref "R64") (pin "1") (pinfunction "1_1") (pintype "passive"))
      (node (ref "TP5") (pin "1") (pinfunction "1_1") (pintype "passive"))
      (node (ref "U1") (pin "C3") (pinfunction "JTAG_TMS_C3") (pintype "passive"))
    )
    (net (code "21") (name "/JTAG_nTRST") (class "Default")
      (node (ref "R62") (pin "1") (pinfunction "1_1") (pintype "passive"))
      (node (ref "TP1") (pin "1") (pinfunction "1_1") (pintype "passive"))
      (node (ref "U1") (pin "C2") (pinfunction "JTAG_TRSTB_C2") (pintype "passive"))
    )
    (net (code "22") (name "/MCU_RSTOUTn") (class "Default")
      (node (ref "R93") (pin "1") (pinfunction "1_1") (pintype "passive"))
    )
    (net (code "23") (name "/MCU_RSTOUTn_R") (class "Default")
      (node (ref "R271") (pin "2") (pinfunction "2_2") (pintype "passive"))
      (node (ref "R69") (pin "1") (pinfunction "1_1") (pintype "passive"))
      (node (ref "R93") (pin "2") (pinfunction "2_2") (pintype "passive"))
      (node (ref "U8") (pin "2") (pinfunction "B_2") (pintype "passive"))
    )
    (net (code "24") (name "/ON_OFF") (class "Default")
      (node (ref "R48") (pin "1") (pinfunction "1_1") (pintype "passive"))
      (node (ref "TP3") (pin "1") (pinfunction "1_1") (pintype "passive"))
      (node (ref "U1") (pin "D12") (pinfunction "SRC_ONOFF_D12") (pintype "passive"))
    )
    (net (code "25") (name "/PCIE_RSTn") (class "Default")
      (node (ref "R158") (pin "2") (pinfunction "2_2") (pintype "passive"))
      (node (ref "R170") (pin "1") (pinfunction "1_1") (pintype "passive"))
    )
    (net (code "26") (name "/PCIE_RSTn_R") (class "Default")
      (node (ref "R170") (pin "2") (pinfunction "2_2") (pintype "passive"))
    )
    (net (code "27") (name "/PMIC_INT") (class "Default")
      (node (ref "U1") (pin "T24") (pinfunction "IPU1_DISP0_DATA12_/_IPU2_DISP0_DATA12_/_<GPIO5_IO06>_T24") (pintype "passive"))
    )
    (net (code "28") (name "/PMIC_ON_REQ") (class "Default")
      (node (ref "D29") (pin "1") (pinfunction "cathode_1") (pintype "passive"))
      (node (ref "R73") (pin "1") (pinfunction "1_1") (pintype "passive"))
      (node (ref "U1") (pin "D11") (pinfunction "SNVS_PMIC_ON_REQ_D11") (pintype "output"))
    )
    (net (code "29") (name "/PMIC_STBY_REQ") (class "Default")
      (node (ref "D28") (pin "2") (pinfunction "ANODE_2") (pintype "passive"))
    )
    (net (code "30") (name "/PMIC_STBY_REQ_CPU") (class "Default")
      (node (ref "D28") (pin "1") (pinfunction "cathode_1") (pintype "passive"))
      (node (ref "R266") (pin "1") (pinfunction "1_1") (pintype "passive"))
      (node (ref "U1") (pin "F11") (pinfunction "CCM_PMIC_STBY_REQ_F11") (pintype "output"))
    )
    (net (code "31") (name "/POK_1V375_OPT") (class "Default")
      (node (ref "R351") (pin "1") (pinfunction "1_1") (pintype "passive"))
    )
    (net (code "32") (name "/POK_3V3_OPT") (class "Default")
      (node (ref "R333") (pin "1") (pinfunction "1_1") (pintype "passive"))
    )
    (net (code "33") (name "/POK_PMIC") (class "Default")
      (node (ref "R177") (pin "1") (pinfunction "1_1") (pintype "passive"))
    )
    (net (code "34") (name "/POK_SYS") (class "Default")
      (node (ref "R177") (pin "2") (pinfunction "2_2") (pintype "passive"))
      (node (ref "R272") (pin "1") (pinfunction "1_1") (pintype "passive"))
      (node (ref "R333") (pin "2") (pinfunction "2_2") (pintype "passive"))
      (node (ref "R351") (pin "2") (pinfunction "2_2") (pintype "passive"))
      (node (ref "U10") (pin "2") (pinfunction "B_2") (pintype "passive"))
    )
    (net (code "35") (name "/POR_Bn") (class "Default")
      (node (ref "D10") (pin "1") (pinfunction "cathode_1") (pintype "passive"))
      (node (ref "R158") (pin "1") (pinfunction "1_1") (pintype "passive"))
      (node (ref "R178") (pin "2") (pinfunction "2_2") (pintype "passive"))
      (node (ref "R225") (pin "1") (pinfunction "1_1") (pintype "passive"))
      (node (ref "R350") (pin "1") (pinfunction "1_1") (pintype "passive"))
      (node (ref "R70") (pin "1") (pinfunction "1_1") (pintype "passive"))
      (node (ref "U1") (pin "C11") (pinfunction "~{SRC_POR}_C11") (pintype "passive"))
      (node (ref "U31") (pin "1") (pinfunction "~{RESE}T_1") (pintype "output"))
    )
    (net (code "36") (name "/POR_CT") (class "Default")
      (node (ref "C413") (pin "1") (pinfunction "1_1") (pintype "passive"))
      (node (ref "U31") (pin "4") (pinfunction "CT_4") (pintype "passive"))
    )
    (net (code "37") (name "/POR_R_Bn") (class "Default")
      (node (ref "R350") (pin "2") (pinfunction "2_2") (pintype "passive"))
      (node (ref "U10") (pin "4") (pinfunction "Y_4") (pintype "passive"))
      (node (ref "U31") (pin "3") (pinfunction "~{MR}_3") (pintype "passive"))
    )
    (net (code "38") (name "/PWRON") (class "Default")
      (node (ref "D29") (pin "2") (pinfunction "ANODE_2") (pintype "passive"))
    )
    (net (code "39") (name "/RGMII_RSTn") (class "Default")
      (node (ref "D10") (pin "2") (pinfunction "ANODE_2") (pintype "passive"))
      (node (ref "R180") (pin "1") (pinfunction "1_1") (pintype "passive"))
    )
    (net (code "40") (name "/RGMII_RSTn_R") (class "Default")
      (node (ref "R180") (pin "2") (pinfunction "2_2") (pintype "passive"))
      (node (ref "U1") (pin "U21") (pinfunction "ENET_RX_EN_/_ESAI_TX_CLK_/_SPDIF_EXT_CLK_/_<GPIO1_IO25>_U21") (pintype "passive"))
    )
    (net (code "41") (name "/RSTINn") (class "Default")
      (node (ref "R68") (pin "1") (pinfunction "1_1") (pintype "passive"))
      (node (ref "U8") (pin "1") (pinfunction "A_1") (pintype "passive"))
    )
    (net (code "42") (name "/RSTINn_BUFF") (class "Default")
      (node (ref "R59") (pin "1") (pinfunction "1_1") (pintype "passive"))
      (node (ref "U10") (pin "1") (pinfunction "A_1") (pintype "passive"))
      (node (ref "U8") (pin "4") (pinfunction "Y_4") (pintype "passive"))
    )
    (net (code "43") (name "/RSTOUTn") (class "Default")
      (node (ref "R144") (pin "2") (pinfunction "2_2") (pintype "passive"))
      (node (ref "U11") (pin "4") (pinfunction "Y_4") (pintype "passive"))
    )
    (net (code "44") (name "/RSTOUTn_BUFF") (class "Default")
      (node (ref "R51") (pin "2") (pinfunction "2_2") (pintype "passive"))
      (node (ref "R70") (pin "2") (pinfunction "2_2") (pintype "passive"))
      (node (ref "U11") (pin "1") (pinfunction "A_1") (pintype "passive"))
      (node (ref "U11") (pin "2") (pinfunction "B_2") (pintype "passive"))
    )
    (net (code "45") (name "/RSTOUTn_R") (class "Default")
      (node (ref "R49") (pin "1") (pinfunction "1_1") (pintype "passive"))
      (node (ref "R51") (pin "1") (pinfunction "1_1") (pintype "passive"))
      (node (ref "U1") (pin "H19") (pinfunction "<EIM_ADDR25>_/_ECSPI4_SS1_/_ECSPI2_RDY_/_IPU1_DI1_PIN12_/_IPU1_DI0_D1_CS_/_GPIO5_IO02_/_HDMI_TX_CEC_LINE_H19") (pintype "bidirectional"))
    )
    (net (code "46") (name "/RTC_XTALI") (class "Default")
      (node (ref "C211") (pin "1") (pinfunction "1_1") (pintype "passive"))
      (node (ref "R168") (pin "1") (pinfunction "1_1") (pintype "passive"))
      (node (ref "U1") (pin "D9") (pinfunction "XTALOSC_RTC_XTALI_D9") (pintype "passive"))
      (node (ref "Y2") (pin "1") (pinfunction "1_1") (pintype "passive"))
    )
    (net (code "47") (name "/RTC_XTALO") (class "Default")
      (node (ref "C212") (pin "1") (pinfunction "1_1") (pintype "passive"))
      (node (ref "R168") (pin "2") (pinfunction "2_2") (pintype "passive"))
      (node (ref "U1") (pin "C9") (pinfunction "XTALOSC_RTC_XTALO_C9") (pintype "output"))
      (node (ref "Y2") (pin "2") (pinfunction "2_2") (pintype "passive"))
    )
    (net (code "48") (name "/SENSE_1V5") (class "Default")
      (node (ref "R302") (pin "1") (pinfunction "1_1") (pintype "passive"))
      (node (ref "R303") (pin "2") (pinfunction "2_2") (pintype "passive"))
      (node (ref "U31") (pin "5") (pinfunction "SENSE1_5") (pintype "passive"))
    )
    (net (code "49") (name "/TAMPER") (class "Default")
      (node (ref "R55") (pin "1") (pinfunction "1_1") (pintype "passive"))
      (node (ref "U1") (pin "E11") (pinfunction "SNVS_TAMPER_E11") (pintype "passive"))
    )
    (net (code "50") (name "/TEST_MODE") (class "Default")
      (node (ref "R56") (pin "2") (pinfunction "2_2") (pintype "passive"))
      (node (ref "U1") (pin "E12") (pinfunction "TCU_TEST_MODE_E12") (pintype "passive"))
    )
    (net (code "51") (name "/USER_LED") (class "Default")
      (node (ref "U1") (pin "E19") (pinfunction "SD1_DATA2_/_ECSPI5_SS1_/_GPT_COMPARE2_/_PWM2_OUT_/_WDOG1_B_/_<GPIO1_IO19>_/_WDOG1_RESET_B_DEB_E19") (pintype "passive"))
    )
    (net (code "52") (name "/VID_IN_CSI1_RSTn") (class "Default")
      (node (ref "R178") (pin "1") (pinfunction "1_1") (pintype "passive"))
      (node (ref "R179") (pin "1") (pinfunction "1_1") (pintype "passive"))
    )
    (net (code "53") (name "/VID_IN_CSI1_RSTn_R") (class "Default")
      (node (ref "R179") (pin "2") (pinfunction "2_2") (pintype "passive"))
    )
    (net (code "54") (name "/WD_OUT") (class "Default")
      (node (ref "R271") (pin "1") (pinfunction "1_1") (pintype "passive"))
      (node (ref "U1") (pin "T2") (pinfunction "ESAI_RX_FS_/_WDOG1_B_/_KEY_COL6_/_CCM_REF_EN_B_/_PWM1_OUT_/_<GPIO1_IO09>_/_SD1_WP_T2") (pintype "bidirectional"))
    )
    (net (code "55") (name "GND") (class "Default")
      (node (ref "C211") (pin "2") (pinfunction "2_2") (pintype "passive"))
      (node (ref "C212") (pin "2") (pinfunction "2_2") (pintype "passive"))
      (node (ref "C386") (pin "2") (pinfunction "2_2") (pintype "passive"))
      (node (ref "C412") (pin "2") (pinfunction "2_2") (pintype "passive"))
      (node (ref "C413") (pin "2") (pinfunction "2_2") (pintype "passive"))
      (node (ref "C83") (pin "2") (pinfunction "2_2") (pintype "passive"))
      (node (ref "C84") (pin "2") (pinfunction "2_2") (pintype "passive"))
      (node (ref "C87") (pin "2") (pinfunction "2_2") (pintype "passive"))
      (node (ref "C89") (pin "2") (pinfunction "2_2") (pintype "passive"))
      (node (ref "JP2") (pin "2") (pinfunction "2_2") (pintype "passive"))
      (node (ref "Q9") (pin "2") (pinfunction "SOURCE_2") (pintype "passive"))
      (node (ref "R144") (pin "1") (pinfunction "1_1") (pintype "passive"))
      (node (ref "R163") (pin "1") (pinfunction "1_1") (pintype "passive"))
      (node (ref "R164") (pin "1") (pinfunction "1_1") (pintype "passive"))
      (node (ref "R166") (pin "1") (pinfunction "1_1") (pintype "passive"))
      (node (ref "R175") (pin "1") (pinfunction "1_1") (pintype "passive"))
      (node (ref "R20") (pin "2") (pinfunction "2_2") (pintype "passive"))
      (node (ref "R303") (pin "1") (pinfunction "1_1") (pintype "passive"))
      (node (ref "R346") (pin "1") (pinfunction "1_1") (pintype "passive"))
      (node (ref "R56") (pin "1") (pinfunction "1_1") (pintype "passive"))
      (node (ref "R58") (pin "1") (pinfunction "1_1") (pintype "passive"))
      (node (ref "R61") (pin "1") (pinfunction "1_1") (pintype "passive"))
      (node (ref "U10") (pin "3") (pinfunction "GND_3") (pintype "power_in"))
      (node (ref "U11") (pin "3") (pinfunction "GND_3") (pintype "power_in"))
      (node (ref "U31") (pin "2") (pinfunction "GND_2") (pintype "passive"))
      (node (ref "U8") (pin "3") (pinfunction "GND_3") (pintype "power_in"))
      (node (ref "Y1") (pin "2") (pinfunction "2_2") (pintype "passive"))
      (node (ref "Y1") (pin "4") (pinfunction "4_4") (pintype "passive"))
    )
    (net (code "56") (name "unconnected-(U1A-IPU1_DISP0_DATA22_{slash}_IPU2_DISP0_DATA22_{slash}_ECSPI1_MISO_{slash}_AUD4_TXFS_{slash}_<GPIO5_IO16>-PadV24)") (class "Default")
      (node (ref "U1") (pin "V24") (pinfunction "IPU1_DISP0_DATA22_/_IPU2_DISP0_DATA22_/_ECSPI1_MISO_/_AUD4_TXFS_/_<GPIO5_IO16>_V24") (pintype "bidirectional+no_connect"))
    )
    (net (code "57") (name "unconnected-(U1A-USB_OTG_ID_{slash}_ENET_RX_ER_{slash}_ESAI_RX_HF_CLK_{slash}_SPDIF_IN_{slash}_ENET_1588_EVENT2_OUT_{slash}_<GPIO1_IO24>-PadW23)") (class "Default")
      (node (ref "U1") (pin "W23") (pinfunction "USB_OTG_ID_/_ENET_RX_ER_/_ESAI_RX_HF_CLK_/_SPDIF_IN_/_ENET_1588_EVENT2_OUT_/_<GPIO1_IO24>_W23") (pintype "passive+no_connect"))
    )
    (net (code "58") (name "unconnected-(U1A-XTALOSC_CLK2_N-PadC5)") (class "Default")
      (node (ref "U1") (pin "C5") (pinfunction "XTALOSC_CLK2_N_C5") (pintype "bidirectional+no_connect"))
    )
    (net (code "59") (name "unconnected-(U1A-XTALOSC_CLK2_P-PadD5)") (class "Default")
      (node (ref "U1") (pin "D5") (pinfunction "XTALOSC_CLK2_P_D5") (pintype "bidirectional+no_connect"))
    )
  )
)
